# 3_Heater_and_Temperature_sensor.net
KiCad netlist of a schematic drawn in Altium Designer
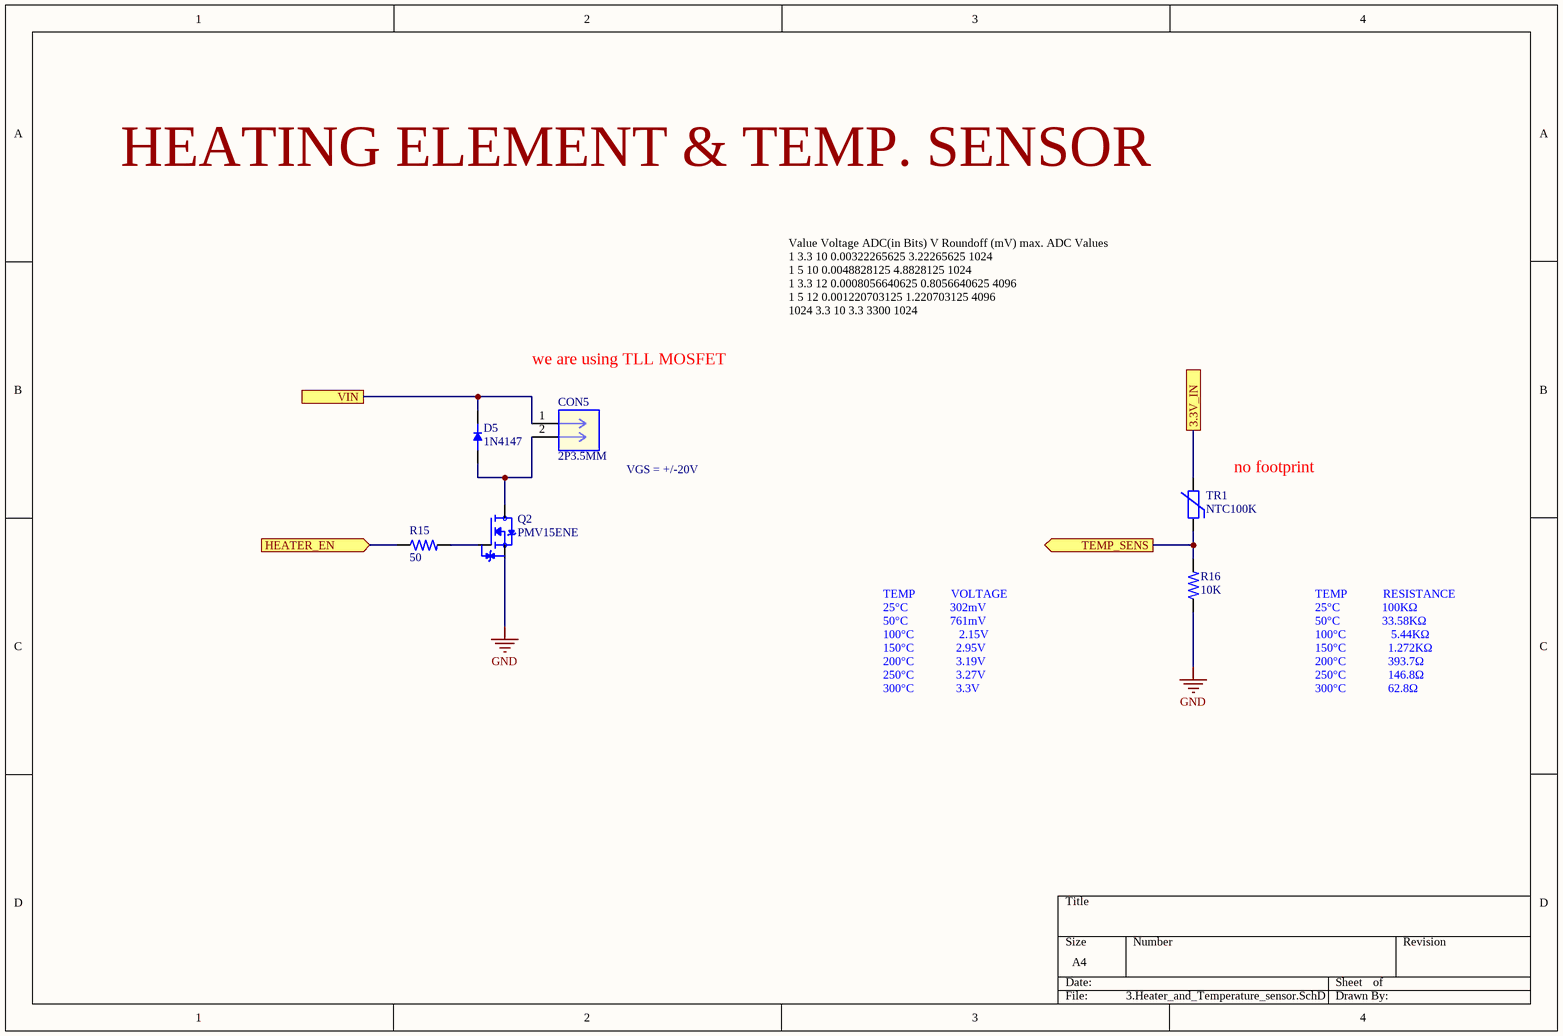
[diagram p0: 3.Heater_and_Temperature_sensor.SchDoc]

(export (version "E")
  (design (tool "Eeschema 10.0.6"))
  (components
    (comp (ref "CON5")
      (value "2P3.5MM")
      (footprint "2P_P3.5mm")
      (fields (field (name "MFR") "Molex"))
      (libsource (lib "Schlib") (part "2P3.5MM"))
    )
    (comp (ref "D5")
      (value "1N4147")
      (footprint "SOD123")
      (fields (field (name "MFR") "Panjit"))
      (libsource (lib "Schlib") (part "1N4147"))
    )
    (comp (ref "Q2")
      (value "PMV15ENE")
      (footprint "SOT23FR")
      (fields (field (name "MFR") "Nexperia"))
      (libsource (lib "Schlib") (part "PMV15ENE"))
    )
    (comp (ref "R15") (value "50") (footprint "R_0603") (libsource (lib "Schlib") (part "R_0603")))
    (comp (ref "R16") (value "10K") (footprint "R_0603") (libsource (lib "Schlib") (part "R_0603")))
    (comp (ref "TR1")
      (value "NTC100K")
      (fields (field (name "MFR") "Bussmann / Eaton"))
      (libsource (lib "Schlib") (part "NTC100K"))
    )
  )
  (nets
    (net (code "1") (name "/3.3V_IN") (class "Default")
      (node (ref "TR1") (pin "1") (pinfunction "1_1") (pintype "passive"))
    )
    (net (code "2") (name "/HEATER_EN") (class "Default")
      (node (ref "R15") (pin "1") (pinfunction "1_1") (pintype "passive"))
    )
    (net (code "3") (name "/TEMP_SENS") (class "Default")
      (node (ref "R16") (pin "2") (pinfunction "2_2") (pintype "passive"))
      (node (ref "TR1") (pin "2") (pinfunction "2_2") (pintype "passive"))
    )
    (net (code "4") (name "/VIN") (class "Default")
      (node (ref "CON5") (pin "1") (pinfunction "1_1") (pintype "passive"))
      (node (ref "D5") (pin "C") (pinfunction "K_C") (pintype "passive"))
    )
    (net (code "5") (name "GND") (class "Default")
      (node (ref "Q2") (pin "3") (pinfunction "S_3") (pintype "passive"))
      (node (ref "R16") (pin "1") (pinfunction "1_1") (pintype "passive"))
    )
    (net (code "6") (name "Net-(Q2-D)") (class "Default")
      (node (ref "CON5") (pin "2") (pinfunction "2_2") (pintype "passive"))
      (node (ref "D5") (pin "A") (pinfunction "A_A") (pintype "passive"))
      (node (ref "Q2") (pin "1") (pinfunction "D_1") (pintype "passive"))
    )
    (net (code "7") (name "Net-(Q2-G)") (class "Default")
      (node (ref "Q2") (pin "2") (pinfunction "G_2") (pintype "passive"))
      (node (ref "R15") (pin "2") (pinfunction "2_2") (pintype "passive"))
    )
  )
)
